# HominiPulseSensorControllerBoard.net
KiCad netlist of a schematic drawn in EAGLE
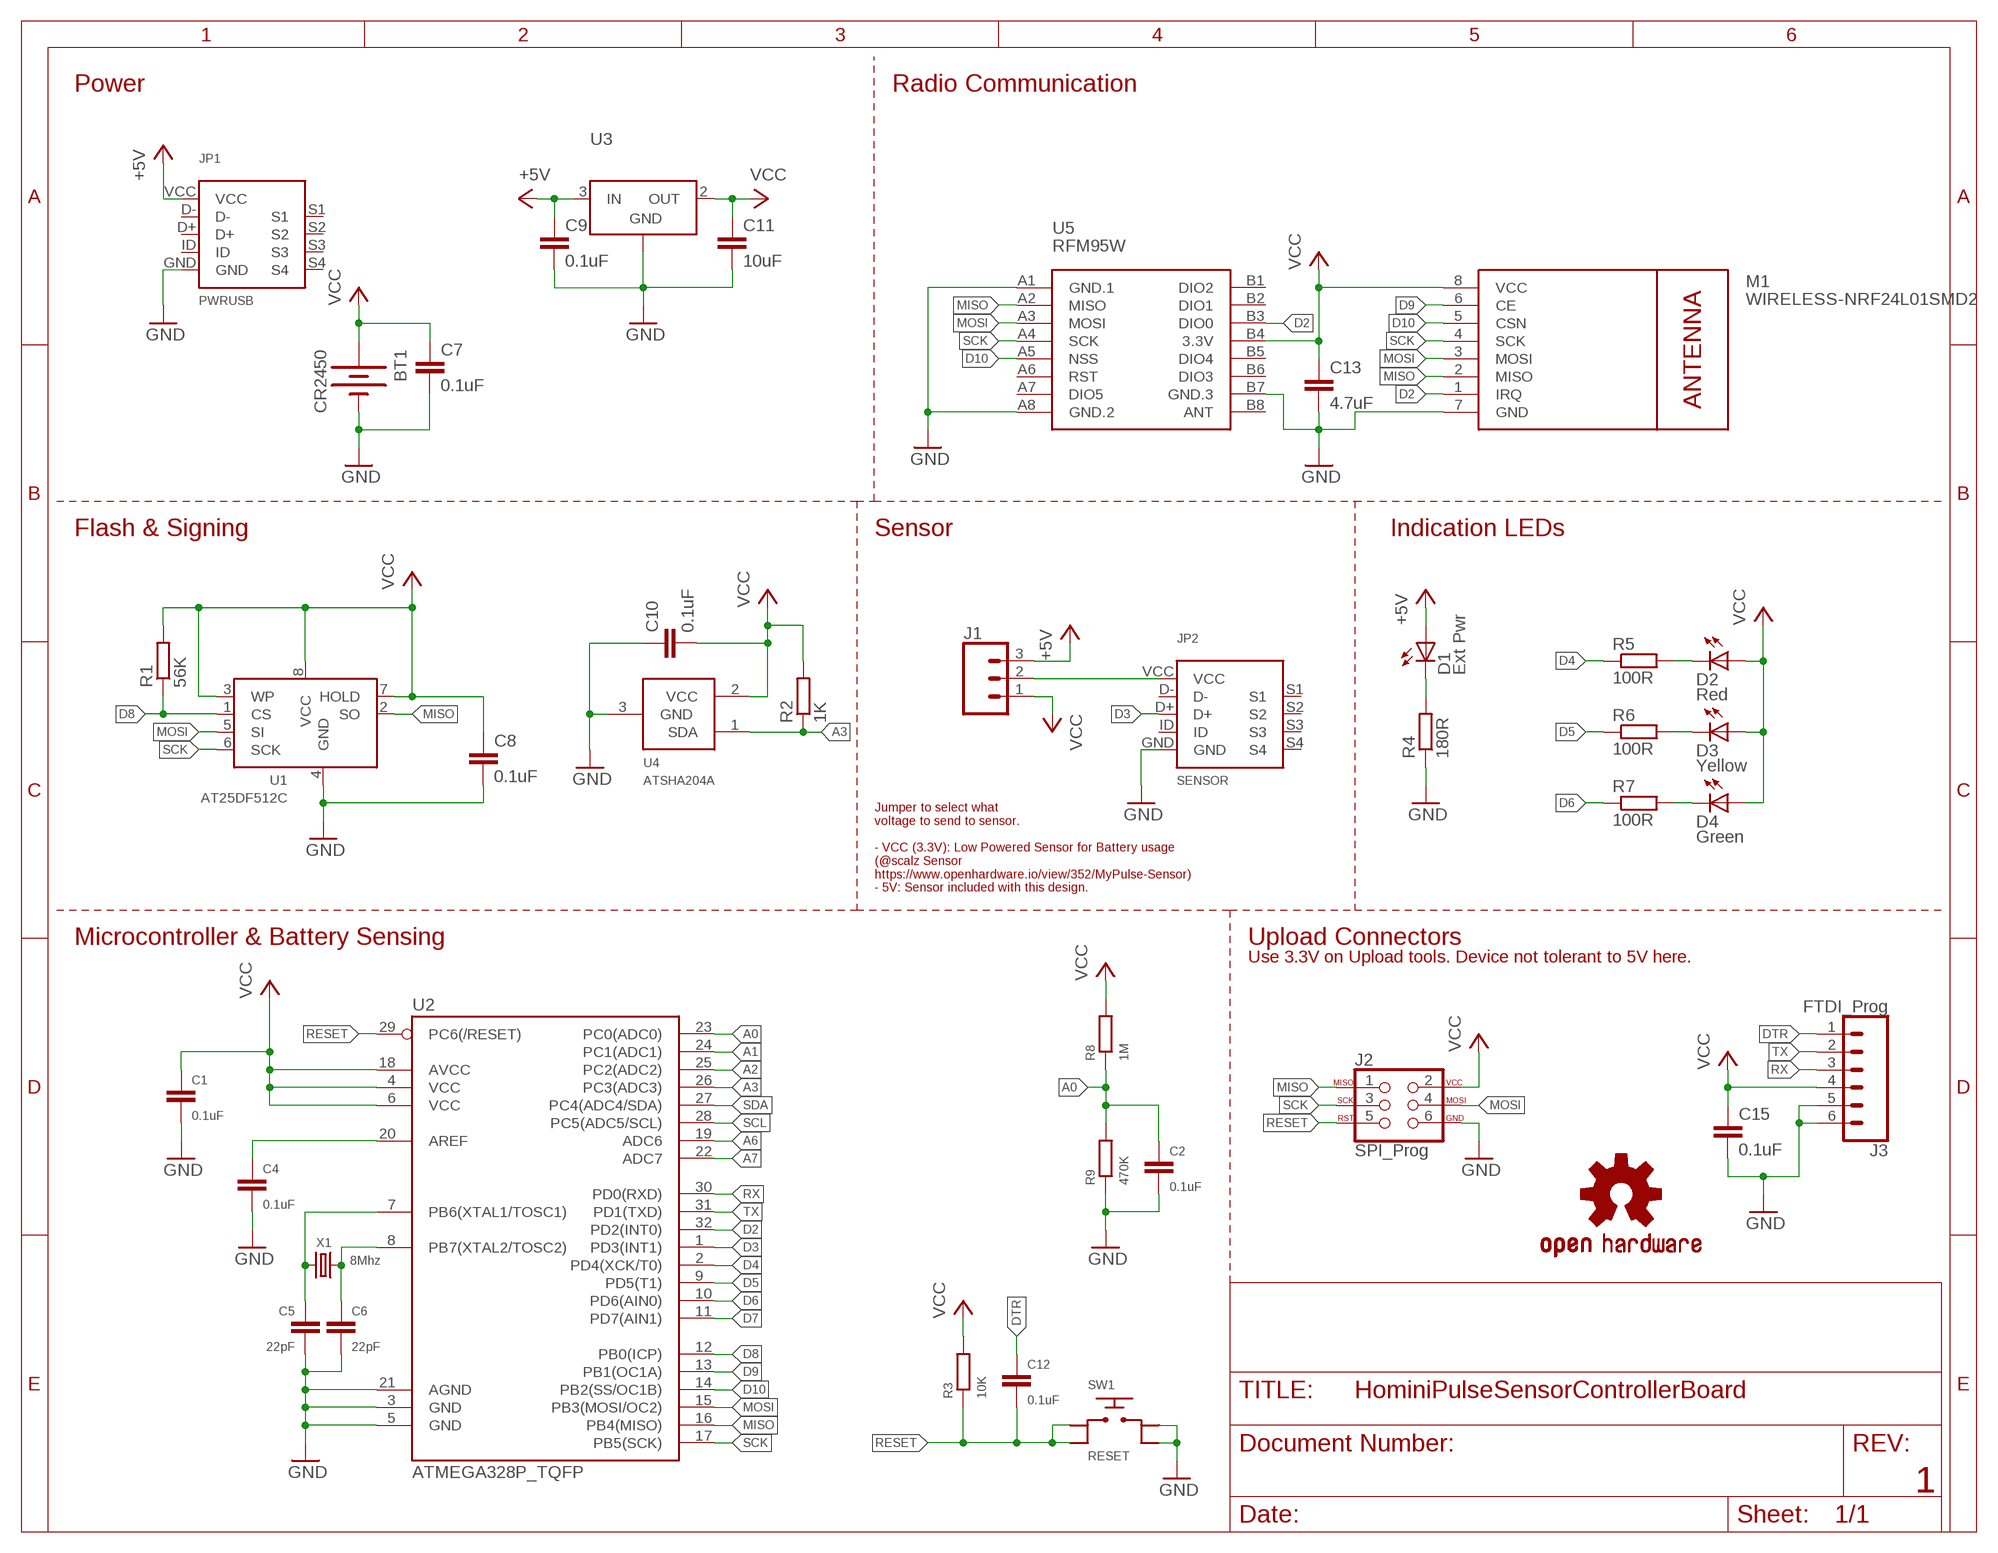
[diagram p0: schematic, sheet 1]

(export (version "E")
  (design (tool "Eeschema 10.0.6"))
  (components
    (comp (ref "BT1")
      (value "CR2450")
      (footprint "eagle-import:BATTCON_24.5MM")
      (libsource (lib "eagle-import") (part "CR2450"))
    )
    (comp (ref "C1")
      (value "0.1uF")
      (footprint "eagle-import:C0603")
      (libsource (lib "eagle-import") (part "C-EUC0603"))
    )
    (comp (ref "C2")
      (value "0.1uF")
      (footprint "eagle-import:C0603")
      (libsource (lib "eagle-import") (part "C-EUC0603"))
    )
    (comp (ref "C4")
      (value "0.1uF")
      (footprint "eagle-import:C0603")
      (libsource (lib "eagle-import") (part "C-EUC0603"))
    )
    (comp (ref "C5")
      (value "22pF")
      (footprint "eagle-import:C0603")
      (libsource (lib "eagle-import") (part "C-EUC0603"))
    )
    (comp (ref "C6")
      (value "22pF")
      (footprint "eagle-import:C0603")
      (libsource (lib "eagle-import") (part "C-EUC0603"))
    )
    (comp (ref "C7")
      (value "0.1uF")
      (footprint "eagle-import:C0603")
      (libsource (lib "eagle-import") (part "C-EUC0603"))
    )
    (comp (ref "C8")
      (value "0.1uF")
      (footprint "eagle-import:C0603")
      (libsource (lib "eagle-import") (part "C-EUC0603"))
    )
    (comp (ref "C9")
      (value "0.1uF")
      (footprint "eagle-import:C0603")
      (libsource (lib "eagle-import") (part "C-EUC0603"))
    )
    (comp (ref "C10")
      (value "0.1uF")
      (footprint "eagle-import:C0603")
      (libsource (lib "eagle-import") (part "C-EUC0603"))
    )
    (comp (ref "C11")
      (value "10uF")
      (footprint "eagle-import:C0603")
      (libsource (lib "eagle-import") (part "C-EUC0603"))
    )
    (comp (ref "C12")
      (value "0.1uF")
      (footprint "eagle-import:C0603")
      (libsource (lib "eagle-import") (part "C-EUC0603"))
    )
    (comp (ref "C13")
      (value "4.7uF")
      (footprint "eagle-import:C0603")
      (libsource (lib "eagle-import") (part "C-EUC0603"))
    )
    (comp (ref "C15")
      (value "0.1uF")
      (footprint "eagle-import:C0603")
      (libsource (lib "eagle-import") (part "C-EUC0603"))
    )
    (comp (ref "D1")
      (value "Ext Pwr")
      (footprint "eagle-import:LED3MM")
      (libsource (lib "eagle-import") (part "LED3MM"))
    )
    (comp (ref "D2")
      (value "Red")
      (footprint "eagle-import:LED3MM")
      (libsource (lib "eagle-import") (part "LED3MM"))
    )
    (comp (ref "D3")
      (value "Yellow")
      (footprint "eagle-import:LED3MM")
      (libsource (lib "eagle-import") (part "LED3MM"))
    )
    (comp (ref "D4")
      (value "Green")
      (footprint "eagle-import:LED3MM")
      (libsource (lib "eagle-import") (part "LED3MM"))
    )
    (comp (ref "J1")
      (value "CONN_03")
      (footprint "eagle-import:1X03")
      (libsource (lib "eagle-import") (part "CONN_03"))
    )
    (comp (ref "J2")
      (value "SPI_Prog")
      (footprint "eagle-import:2X3")
      (libsource (lib "eagle-import") (part "AVR_SPI_PROG_3X2PTH"))
    )
    (comp (ref "J3")
      (value "FTDI_Prog")
      (footprint "eagle-import:1X06_NO_SILK")
      (libsource (lib "eagle-import") (part "CONN_06NO_SILK_FEMALE_PTH"))
    )
    (comp (ref "JP1")
      (value "PWRUSB")
      (footprint "eagle-import:MICROUSBSMD")
      (libsource (lib "eagle-import") (part "MICROUSBSMD"))
    )
    (comp (ref "JP2")
      (value "SENSOR")
      (footprint "eagle-import:MICROUSBSMD")
      (libsource (lib "eagle-import") (part "MICROUSBSMD"))
    )
    (comp (ref "LOGO1")
      (value "OSHW-LOGOM")
      (footprint "eagle-import:OSHW-LOGO-M")
      (libsource (lib "eagle-import") (part "OSHW-LOGOM"))
    )
    (comp (ref "M1")
      (value "WIRELESS-NRF24L01SMD2")
      (footprint "eagle-import:WIRELESS-NRF24L01-SMD-2")
      (libsource (lib "eagle-import") (part "WIRELESS-NRF24L01SMD2"))
    )
    (comp (ref "R1")
      (value "56K")
      (footprint "eagle-import:R0603")
      (libsource (lib "eagle-import") (part "R-EU_R0603"))
    )
    (comp (ref "R2")
      (value "1K")
      (footprint "eagle-import:R0603")
      (libsource (lib "eagle-import") (part "R-EU_R0603"))
    )
    (comp (ref "R3")
      (value "10K")
      (footprint "eagle-import:R0603")
      (libsource (lib "eagle-import") (part "R-EU_R0603"))
    )
    (comp (ref "R4")
      (value "180R")
      (footprint "eagle-import:R0603")
      (libsource (lib "eagle-import") (part "R-EU_R0603"))
    )
    (comp (ref "R5")
      (value "100R")
      (footprint "eagle-import:R0603")
      (libsource (lib "eagle-import") (part "R-EU_R0603"))
    )
    (comp (ref "R6")
      (value "100R")
      (footprint "eagle-import:R0603")
      (libsource (lib "eagle-import") (part "R-EU_R0603"))
    )
    (comp (ref "R7")
      (value "100R")
      (footprint "eagle-import:R0603")
      (libsource (lib "eagle-import") (part "R-EU_R0603"))
    )
    (comp (ref "R8")
      (value "1M")
      (footprint "eagle-import:R0603")
      (libsource (lib "eagle-import") (part "R-EU_R0603"))
    )
    (comp (ref "R9")
      (value "470K")
      (footprint "eagle-import:R0603")
      (libsource (lib "eagle-import") (part "R-EU_R0603"))
    )
    (comp (ref "SW1")
      (value "RESET")
      (footprint "eagle-import:SMD5X5X1.5MM")
      (libsource (lib "eagle-import") (part "SMD5X5X1.5MM"))
    )
    (comp (ref "U1")
      (value "AT25DF512C")
      (footprint "eagle-import:SOIC-8")
      (libsource (lib "eagle-import") (part "AT25DF512C"))
    )
    (comp (ref "U2")
      (value "ATMEGA328P_TQFP")
      (footprint "eagle-import:TQFP32-08")
      (libsource (lib "eagle-import") (part "ATMEGA328P_TQFP"))
    )
    (comp (ref "U3")
      (value "LD1117V33")
      (footprint "eagle-import:SOC-223")
      (libsource (lib "eagle-import") (part "LD1117V33"))
    )
    (comp (ref "U4")
      (value "ATSHA204A")
      (footprint "eagle-import:SOT23")
      (libsource (lib "eagle-import") (part "ATSHA204A"))
    )
    (comp (ref "U5")
      (value "RFM95W")
      (footprint "eagle-import:WIRELESS-LORA-RFM95W#SMD")
      (libsource (lib "eagle-import") (part "WIRELESS-LORA-RFM95W#SMD"))
    )
    (comp (ref "X1")
      (value "8Mhz")
      (footprint "eagle-import:HC-49S-SMT")
      (libsource (lib "eagle-import") (part "HC-49S-SMT"))
    )
  )
  (nets
    (net (code "1") (name "+5V") (class "Default")
      (node (ref "C9") (pin "1") (pinfunction "1_1") (pintype "passive"))
      (node (ref "D1") (pin "A") (pinfunction "A_A") (pintype "passive"))
      (node (ref "J1") (pin "3") (pinfunction "3_3") (pintype "passive"))
      (node (ref "JP1") (pin "VCC") (pinfunction "VCC_VCC") (pintype "power_in"))
      (node (ref "U3") (pin "3") (pinfunction "IN_3") (pintype "bidirectional"))
    )
    (net (code "2") (name "A0") (class "Default")
      (node (ref "C2") (pin "1") (pinfunction "1_1") (pintype "passive"))
      (node (ref "R8") (pin "1") (pinfunction "1_1") (pintype "passive"))
      (node (ref "R9") (pin "2") (pinfunction "2_2") (pintype "passive"))
      (node (ref "U2") (pin "23") (pinfunction "PC0(ADC0)_23") (pintype "bidirectional"))
    )
    (net (code "3") (name "A1") (class "Default")
      (node (ref "U2") (pin "24") (pinfunction "PC1(ADC1)_24") (pintype "bidirectional"))
    )
    (net (code "4") (name "A2") (class "Default")
      (node (ref "U2") (pin "25") (pinfunction "PC2(ADC2)_25") (pintype "bidirectional"))
    )
    (net (code "5") (name "A3") (class "Default")
      (node (ref "R2") (pin "1") (pinfunction "1_1") (pintype "passive"))
      (node (ref "U2") (pin "26") (pinfunction "PC3(ADC3)_26") (pintype "bidirectional"))
      (node (ref "U4") (pin "1") (pinfunction "SDA_1") (pintype "bidirectional"))
    )
    (net (code "6") (name "A6") (class "Default")
      (node (ref "U2") (pin "19") (pinfunction "ADC6_19") (pintype "bidirectional"))
    )
    (net (code "7") (name "A7") (class "Default")
      (node (ref "U2") (pin "22") (pinfunction "ADC7_22") (pintype "bidirectional"))
    )
    (net (code "8") (name "D2") (class "Default")
      (node (ref "M1") (pin "1") (pinfunction "IRQ_1") (pintype "bidirectional"))
      (node (ref "U2") (pin "32") (pinfunction "PD2(INT0)_32") (pintype "bidirectional"))
      (node (ref "U5") (pin "B3") (pinfunction "DIO0_B3") (pintype "bidirectional"))
    )
    (net (code "9") (name "D3") (class "Default")
      (node (ref "JP2") (pin "D+") (pinfunction "D+_D+") (pintype "bidirectional"))
      (node (ref "U2") (pin "1") (pinfunction "PD3(INT1)_1") (pintype "bidirectional"))
    )
    (net (code "10") (name "D4") (class "Default")
      (node (ref "R5") (pin "1") (pinfunction "1_1") (pintype "passive"))
      (node (ref "U2") (pin "2") (pinfunction "PD4(XCK/T0)_2") (pintype "bidirectional"))
    )
    (net (code "11") (name "D5") (class "Default")
      (node (ref "R6") (pin "1") (pinfunction "1_1") (pintype "passive"))
      (node (ref "U2") (pin "9") (pinfunction "PD5(T1)_9") (pintype "bidirectional"))
    )
    (net (code "12") (name "D6") (class "Default")
      (node (ref "R7") (pin "1") (pinfunction "1_1") (pintype "passive"))
      (node (ref "U2") (pin "10") (pinfunction "PD6(AIN0)_10") (pintype "bidirectional"))
    )
    (net (code "13") (name "D7") (class "Default")
      (node (ref "U2") (pin "11") (pinfunction "PD7(AIN1)_11") (pintype "bidirectional"))
    )
    (net (code "14") (name "D8") (class "Default")
      (node (ref "R1") (pin "1") (pinfunction "1_1") (pintype "passive"))
      (node (ref "U1") (pin "1") (pinfunction "CS_1") (pintype "bidirectional"))
      (node (ref "U2") (pin "12") (pinfunction "PB0(ICP)_12") (pintype "bidirectional"))
    )
    (net (code "15") (name "D9") (class "Default")
      (node (ref "M1") (pin "6") (pinfunction "CE_6") (pintype "bidirectional"))
      (node (ref "U2") (pin "13") (pinfunction "PB1(OC1A)_13") (pintype "bidirectional"))
    )
    (net (code "16") (name "D10") (class "Default")
      (node (ref "M1") (pin "5") (pinfunction "CSN_5") (pintype "bidirectional"))
      (node (ref "U2") (pin "14") (pinfunction "PB2(SS/OC1B)_14") (pintype "bidirectional"))
      (node (ref "U5") (pin "A5") (pinfunction "NSS_A5") (pintype "bidirectional"))
    )
    (net (code "17") (name "DTR") (class "Default")
      (node (ref "C12") (pin "1") (pinfunction "1_1") (pintype "passive"))
      (node (ref "J3") (pin "1") (pinfunction "1_1") (pintype "passive"))
    )
    (net (code "18") (name "GND") (class "Default")
      (node (ref "BT1") (pin "2") (pinfunction "-_2") (pintype "power_in"))
      (node (ref "C1") (pin "2") (pinfunction "2_2") (pintype "passive"))
      (node (ref "C10") (pin "1") (pinfunction "1_1") (pintype "passive"))
      (node (ref "C11") (pin "2") (pinfunction "2_2") (pintype "passive"))
      (node (ref "C13") (pin "2") (pinfunction "2_2") (pintype "passive"))
      (node (ref "C15") (pin "2") (pinfunction "2_2") (pintype "passive"))
      (node (ref "C2") (pin "2") (pinfunction "2_2") (pintype "passive"))
      (node (ref "C4") (pin "2") (pinfunction "2_2") (pintype "passive"))
      (node (ref "C5") (pin "2") (pinfunction "2_2") (pintype "passive"))
      (node (ref "C6") (pin "2") (pinfunction "2_2") (pintype "passive"))
      (node (ref "C7") (pin "2") (pinfunction "2_2") (pintype "passive"))
      (node (ref "C8") (pin "2") (pinfunction "2_2") (pintype "passive"))
      (node (ref "C9") (pin "2") (pinfunction "2_2") (pintype "passive"))
      (node (ref "J2") (pin "6") (pinfunction "6_6") (pintype "passive"))
      (node (ref "J3") (pin "5") (pinfunction "5_5") (pintype "passive"))
      (node (ref "J3") (pin "6") (pinfunction "6_6") (pintype "passive"))
      (node (ref "JP1") (pin "GND") (pinfunction "GND_GND") (pintype "power_in"))
      (node (ref "JP2") (pin "GND") (pinfunction "GND_GND") (pintype "power_in"))
      (node (ref "M1") (pin "7") (pinfunction "GND_7") (pintype "power_in"))
      (node (ref "R4") (pin "1") (pinfunction "1_1") (pintype "passive"))
      (node (ref "R9") (pin "1") (pinfunction "1_1") (pintype "passive"))
      (node (ref "SW1") (pin "3") (pinfunction "3_3") (pintype "bidirectional"))
      (node (ref "SW1") (pin "4") (pinfunction "4_4") (pintype "bidirectional"))
      (node (ref "U1") (pin "4") (pinfunction "GND_4") (pintype "power_in"))
      (node (ref "U2") (pin "21") (pinfunction "AGND_21") (pintype "bidirectional"))
      (node (ref "U2") (pin "3") (pinfunction "GND_3") (pintype "bidirectional"))
      (node (ref "U2") (pin "5") (pinfunction "GND_5") (pintype "bidirectional"))
      (node (ref "U3") (pin "1") (pinfunction "GND_1") (pintype "bidirectional"))
      (node (ref "U4") (pin "3") (pinfunction "GND_3") (pintype "bidirectional"))
      (node (ref "U5") (pin "A1") (pinfunction "GND.1_A1") (pintype "power_in"))
      (node (ref "U5") (pin "A8") (pinfunction "GND.2_A8") (pintype "power_in"))
      (node (ref "U5") (pin "B7") (pinfunction "GND.3_B7") (pintype "power_in"))
    )
    (net (code "19") (name "MISO") (class "Default")
      (node (ref "J2") (pin "1") (pinfunction "1_1") (pintype "passive"))
      (node (ref "M1") (pin "2") (pinfunction "MISO_2") (pintype "bidirectional"))
      (node (ref "U1") (pin "2") (pinfunction "SO_2") (pintype "bidirectional"))
      (node (ref "U2") (pin "16") (pinfunction "PB4(MISO)_16") (pintype "bidirectional"))
      (node (ref "U5") (pin "A2") (pinfunction "MISO_A2") (pintype "bidirectional"))
    )
    (net (code "20") (name "MOSI") (class "Default")
      (node (ref "J2") (pin "4") (pinfunction "4_4") (pintype "passive"))
      (node (ref "M1") (pin "3") (pinfunction "MOSI_3") (pintype "bidirectional"))
      (node (ref "U1") (pin "5") (pinfunction "SI_5") (pintype "bidirectional"))
      (node (ref "U2") (pin "15") (pinfunction "PB3(MOSI/OC2)_15") (pintype "bidirectional"))
      (node (ref "U5") (pin "A3") (pinfunction "MOSI_A3") (pintype "bidirectional"))
    )
    (net (code "21") (name "Net-(D1-C)") (class "Default")
      (node (ref "D1") (pin "K") (pinfunction "C_K") (pintype "passive"))
      (node (ref "R4") (pin "2") (pinfunction "2_2") (pintype "passive"))
    )
    (net (code "22") (name "Net-(D2-C)") (class "Default")
      (node (ref "D2") (pin "K") (pinfunction "C_K") (pintype "passive"))
      (node (ref "R5") (pin "2") (pinfunction "2_2") (pintype "passive"))
    )
    (net (code "23") (name "Net-(D3-C)") (class "Default")
      (node (ref "D3") (pin "K") (pinfunction "C_K") (pintype "passive"))
      (node (ref "R6") (pin "2") (pinfunction "2_2") (pintype "passive"))
    )
    (net (code "24") (name "Net-(D4-C)") (class "Default")
      (node (ref "D4") (pin "K") (pinfunction "C_K") (pintype "passive"))
      (node (ref "R7") (pin "2") (pinfunction "2_2") (pintype "passive"))
    )
    (net (code "25") (name "Net-(J1-Pad2)") (class "Default")
      (node (ref "J1") (pin "2") (pinfunction "2_2") (pintype "passive"))
      (node (ref "JP2") (pin "VCC") (pinfunction "VCC_VCC") (pintype "power_in"))
    )
    (net (code "26") (name "Net-(U2-AREF)") (class "Default")
      (node (ref "C4") (pin "1") (pinfunction "1_1") (pintype "passive"))
      (node (ref "U2") (pin "20") (pinfunction "AREF_20") (pintype "bidirectional"))
    )
    (net (code "27") (name "Net-(U2-PB6(XTAL1{slash}TOSC1))") (class "Default")
      (node (ref "C5") (pin "1") (pinfunction "1_1") (pintype "passive"))
      (node (ref "U2") (pin "7") (pinfunction "PB6(XTAL1/TOSC1)_7") (pintype "bidirectional"))
      (node (ref "X1") (pin "2") (pinfunction "2_2") (pintype "passive"))
    )
    (net (code "28") (name "Net-(U2-PB7(XTAL2{slash}TOSC2))") (class "Default")
      (node (ref "C6") (pin "1") (pinfunction "1_1") (pintype "passive"))
      (node (ref "U2") (pin "8") (pinfunction "PB7(XTAL2/TOSC2)_8") (pintype "bidirectional"))
      (node (ref "X1") (pin "1") (pinfunction "1_1") (pintype "passive"))
    )
    (net (code "29") (name "RESET") (class "Default")
      (node (ref "C12") (pin "2") (pinfunction "2_2") (pintype "passive"))
      (node (ref "J2") (pin "5") (pinfunction "5_5") (pintype "passive"))
      (node (ref "R3") (pin "1") (pinfunction "1_1") (pintype "passive"))
      (node (ref "SW1") (pin "1") (pinfunction "1_1") (pintype "bidirectional"))
      (node (ref "SW1") (pin "2") (pinfunction "2_2") (pintype "bidirectional"))
      (node (ref "U2") (pin "29") (pinfunction "PC6(/RESET)_29") (pintype "bidirectional"))
    )
    (net (code "30") (name "RX") (class "Default")
      (node (ref "J3") (pin "3") (pinfunction "3_3") (pintype "passive"))
      (node (ref "U2") (pin "30") (pinfunction "PD0(RXD)_30") (pintype "bidirectional"))
    )
    (net (code "31") (name "SCK") (class "Default")
      (node (ref "J2") (pin "3") (pinfunction "3_3") (pintype "passive"))
      (node (ref "M1") (pin "4") (pinfunction "SCK_4") (pintype "bidirectional"))
      (node (ref "U1") (pin "6") (pinfunction "SCK_6") (pintype "bidirectional"))
      (node (ref "U2") (pin "17") (pinfunction "PB5(SCK)_17") (pintype "bidirectional"))
      (node (ref "U5") (pin "A4") (pinfunction "SCK_A4") (pintype "bidirectional"))
    )
    (net (code "32") (name "SCL") (class "Default")
      (node (ref "U2") (pin "28") (pinfunction "PC5(ADC5/SCL)_28") (pintype "bidirectional"))
    )
    (net (code "33") (name "SDA") (class "Default")
      (node (ref "U2") (pin "27") (pinfunction "PC4(ADC4/SDA)_27") (pintype "bidirectional"))
    )
    (net (code "34") (name "TX") (class "Default")
      (node (ref "J3") (pin "2") (pinfunction "2_2") (pintype "passive"))
      (node (ref "U2") (pin "31") (pinfunction "PD1(TXD)_31") (pintype "bidirectional"))
    )
    (net (code "35") (name "VCC") (class "Default")
      (node (ref "BT1") (pin "1") (pinfunction "+_1") (pintype "power_in"))
      (node (ref "C1") (pin "1") (pinfunction "1_1") (pintype "passive"))
      (node (ref "C10") (pin "2") (pinfunction "2_2") (pintype "passive"))
      (node (ref "C11") (pin "1") (pinfunction "1_1") (pintype "passive"))
      (node (ref "C13") (pin "1") (pinfunction "1_1") (pintype "passive"))
      (node (ref "C15") (pin "1") (pinfunction "1_1") (pintype "passive"))
      (node (ref "C7") (pin "1") (pinfunction "1_1") (pintype "passive"))
      (node (ref "C8") (pin "1") (pinfunction "1_1") (pintype "passive"))
      (node (ref "D2") (pin "A") (pinfunction "A_A") (pintype "passive"))
      (node (ref "D3") (pin "A") (pinfunction "A_A") (pintype "passive"))
      (node (ref "D4") (pin "A") (pinfunction "A_A") (pintype "passive"))
      (node (ref "J1") (pin "1") (pinfunction "1_1") (pintype "passive"))
      (node (ref "J2") (pin "2") (pinfunction "2_2") (pintype "passive"))
      (node (ref "J3") (pin "4") (pinfunction "4_4") (pintype "passive"))
      (node (ref "M1") (pin "8") (pinfunction "VCC_8") (pintype "power_in"))
      (node (ref "R1") (pin "2") (pinfunction "2_2") (pintype "passive"))
      (node (ref "R2") (pin "2") (pinfunction "2_2") (pintype "passive"))
      (node (ref "R3") (pin "2") (pinfunction "2_2") (pintype "passive"))
      (node (ref "R8") (pin "2") (pinfunction "2_2") (pintype "passive"))
      (node (ref "U1") (pin "3") (pinfunction "WP_3") (pintype "bidirectional"))
      (node (ref "U1") (pin "7") (pinfunction "HOLD_7") (pintype "bidirectional"))
      (node (ref "U1") (pin "8") (pinfunction "VCC_8") (pintype "power_in"))
      (node (ref "U2") (pin "18") (pinfunction "AVCC_18") (pintype "bidirectional"))
      (node (ref "U2") (pin "4") (pinfunction "VCC_4") (pintype "bidirectional"))
      (node (ref "U2") (pin "6") (pinfunction "VCC_6") (pintype "bidirectional"))
      (node (ref "U3") (pin "2") (pinfunction "OUT_2") (pintype "bidirectional"))
      (node (ref "U4") (pin "2") (pinfunction "VCC_2") (pintype "bidirectional"))
      (node (ref "U5") (pin "B4") (pinfunction "3.3V_B4") (pintype "power_in"))
    )
    (net (code "36") (name "unconnected-(JP1-PadD+)") (class "Default")
      (node (ref "JP1") (pin "D+") (pinfunction "D+_D+") (pintype "bidirectional"))
    )
    (net (code "37") (name "unconnected-(JP1-PadD-)") (class "Default")
      (node (ref "JP1") (pin "D-") (pinfunction "D-_D-") (pintype "bidirectional"))
    )
    (net (code "38") (name "unconnected-(JP1-PadID)") (class "Default")
      (node (ref "JP1") (pin "ID") (pinfunction "ID_ID") (pintype "bidirectional"))
    )
    (net (code "39") (name "unconnected-(JP1-PadS1)") (class "Default")
      (node (ref "JP1") (pin "S1") (pinfunction "S1_S1") (pintype "bidirectional"))
    )
    (net (code "40") (name "unconnected-(JP1-PadS2)") (class "Default")
      (node (ref "JP1") (pin "S2") (pinfunction "S2_S2") (pintype "bidirectional"))
    )
    (net (code "41") (name "unconnected-(JP1-PadS3)") (class "Default")
      (node (ref "JP1") (pin "S3") (pinfunction "S3_S3") (pintype "bidirectional"))
    )
    (net (code "42") (name "unconnected-(JP1-PadS4)") (class "Default")
      (node (ref "JP1") (pin "S4") (pinfunction "S4_S4") (pintype "bidirectional"))
    )
    (net (code "43") (name "unconnected-(JP2-PadD-)") (class "Default")
      (node (ref "JP2") (pin "D-") (pinfunction "D-_D-") (pintype "bidirectional"))
    )
    (net (code "44") (name "unconnected-(JP2-PadID)") (class "Default")
      (node (ref "JP2") (pin "ID") (pinfunction "ID_ID") (pintype "bidirectional"))
    )
    (net (code "45") (name "unconnected-(JP2-PadS1)") (class "Default")
      (node (ref "JP2") (pin "S1") (pinfunction "S1_S1") (pintype "bidirectional"))
    )
    (net (code "46") (name "unconnected-(JP2-PadS2)") (class "Default")
      (node (ref "JP2") (pin "S2") (pinfunction "S2_S2") (pintype "bidirectional"))
    )
    (net (code "47") (name "unconnected-(JP2-PadS3)") (class "Default")
      (node (ref "JP2") (pin "S3") (pinfunction "S3_S3") (pintype "bidirectional"))
    )
    (net (code "48") (name "unconnected-(JP2-PadS4)") (class "Default")
      (node (ref "JP2") (pin "S4") (pinfunction "S4_S4") (pintype "bidirectional"))
    )
    (net (code "49") (name "unconnected-(U5-ANT-PadB8)") (class "Default")
      (node (ref "U5") (pin "B8") (pinfunction "ANT_B8") (pintype "passive"))
    )
    (net (code "50") (name "unconnected-(U5-DIO1-PadB2)") (class "Default")
      (node (ref "U5") (pin "B2") (pinfunction "DIO1_B2") (pintype "bidirectional"))
    )
    (net (code "51") (name "unconnected-(U5-DIO2-PadB1)") (class "Default")
      (node (ref "U5") (pin "B1") (pinfunction "DIO2_B1") (pintype "bidirectional"))
    )
    (net (code "52") (name "unconnected-(U5-DIO3-PadB6)") (class "Default")
      (node (ref "U5") (pin "B6") (pinfunction "DIO3_B6") (pintype "bidirectional"))
    )
    (net (code "53") (name "unconnected-(U5-DIO4-PadB5)") (class "Default")
      (node (ref "U5") (pin "B5") (pinfunction "DIO4_B5") (pintype "bidirectional"))
    )
    (net (code "54") (name "unconnected-(U5-DIO5-PadA7)") (class "Default")
      (node (ref "U5") (pin "A7") (pinfunction "DIO5_A7") (pintype "bidirectional"))
    )
    (net (code "55") (name "unconnected-(U5-RST-PadA6)") (class "Default")
      (node (ref "U5") (pin "A6") (pinfunction "RST_A6") (pintype "bidirectional"))
    )
  )
)
